# Slot_Detectors.net
KiCad netlist of a schematic drawn in Altium Designer
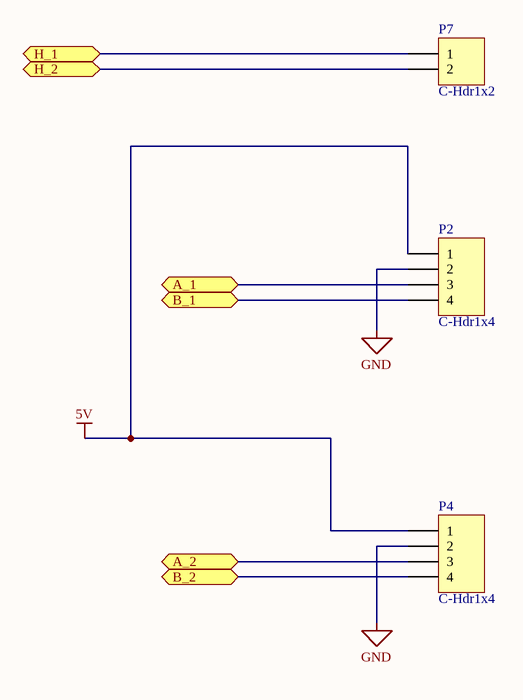
[diagram p0: Slot_Detectors.SchDoc]

(export (version "E")
  (design (tool "Eeschema 10.0.6"))
  (components
    (comp (ref "P2")
      (value "C-Hdr1x4")
      (footprint "HDR1X4_LGE1.0")
      (description "Header, 4-Pin")
      (fields (field (name "PUBLISHER") "Altium Limited"))
      (libsource (lib "PartsDatabaseV16.1") (part "C-Hdr1x4"))
    )
    (comp (ref "P4")
      (value "C-Hdr1x4")
      (footprint "HDR1X4_LGE1.0")
      (description "Header, 4-Pin")
      (fields (field (name "PUBLISHER") "Altium Limited"))
      (libsource (lib "PartsDatabaseV16.1") (part "C-Hdr1x4"))
    )
    (comp (ref "P7")
      (value "C-Hdr1x2")
      (footprint "HDR1X2_LGE1.0")
      (description "Header, 2-Pin")
      (fields (field (name "PUBLISHER") "Altium Limited"))
      (libsource (lib "PartsDatabaseV16.1") (part "C-Hdr1x2"))
    )
  )
  (nets
    (net (code "1") (name "/A_1") (class "Default")
      (node (ref "P2") (pin "3") (pinfunction "3_3") (pintype "passive"))
    )
    (net (code "2") (name "/A_2") (class "Default")
      (node (ref "P4") (pin "3") (pinfunction "3_3") (pintype "passive"))
    )
    (net (code "3") (name "/B_1") (class "Default")
      (node (ref "P2") (pin "4") (pinfunction "4_4") (pintype "passive"))
    )
    (net (code "4") (name "/B_2") (class "Default")
      (node (ref "P4") (pin "4") (pinfunction "4_4") (pintype "passive"))
    )
    (net (code "5") (name "/H_1") (class "Default")
      (node (ref "P7") (pin "1") (pinfunction "1_1") (pintype "passive"))
    )
    (net (code "6") (name "/H_2") (class "Default")
      (node (ref "P7") (pin "2") (pinfunction "2_2") (pintype "passive"))
    )
    (net (code "7") (name "5V") (class "Default")
      (node (ref "P2") (pin "1") (pinfunction "1_1") (pintype "passive"))
      (node (ref "P4") (pin "1") (pinfunction "1_1") (pintype "passive"))
    )
    (net (code "8") (name "GND") (class "Default")
      (node (ref "P2") (pin "2") (pinfunction "2_2") (pintype "passive"))
      (node (ref "P4") (pin "2") (pinfunction "2_2") (pintype "passive"))
    )
  )
)
